# CMSIS-DAP_JX_copy.net
KiCad netlist of a schematic drawn in Altium Designer
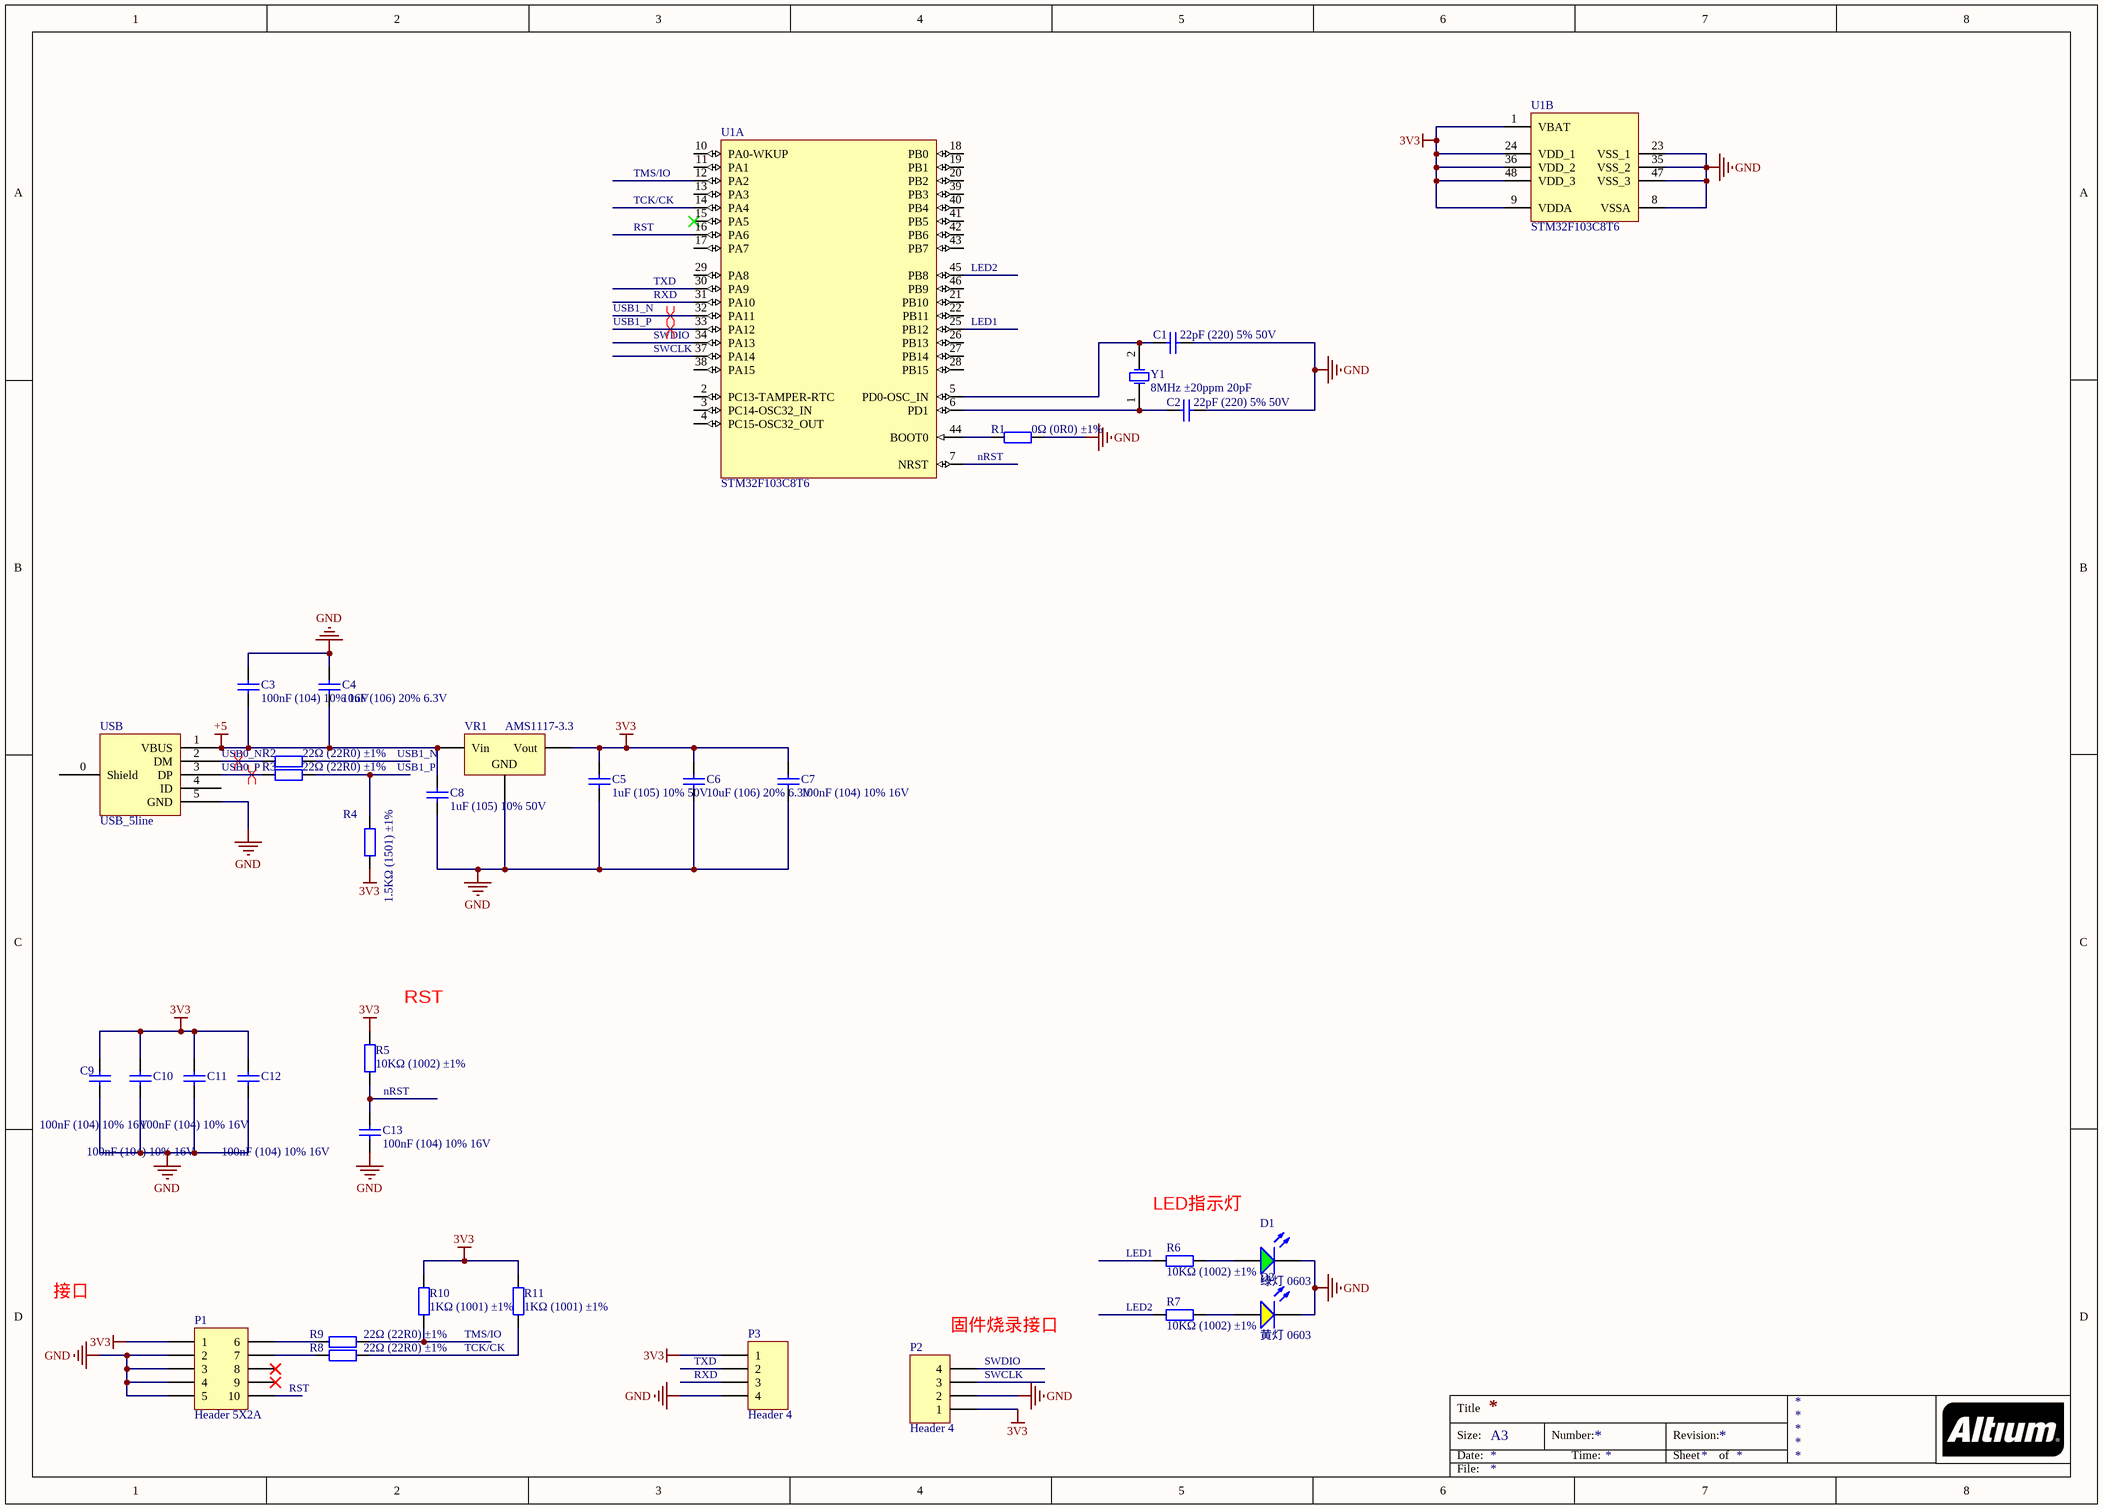
[diagram p0: CMSIS-DAP_JX+copy.schdoc]

(export (version "E")
  (design (tool "Eeschema 10.0.6"))
  (components
    (comp (ref "C1")
      (value "22pF (220) 5% 50V")
      (footprint "0402_C")
      (description "贴片电容")
      (libsource (lib "Miscellaneous Devices LC") (part "0402 22pF (220) 5% 50V"))
    )
    (comp (ref "C2")
      (value "22pF (220) 5% 50V")
      (footprint "0402_C")
      (description "贴片电容")
      (libsource (lib "Miscellaneous Devices LC") (part "0402 22pF (220) 5% 50V"))
    )
    (comp (ref "C3")
      (value "100nF (104) 10% 16V")
      (footprint "0402_C")
      (description "贴片电容")
      (libsource (lib "Miscellaneous Devices LC") (part "0402 100nF (104) 10% 16V"))
    )
    (comp (ref "C4")
      (value "10uF (106) 20% 6.3V")
      (footprint "0402_C")
      (description "贴片电容")
      (libsource (lib "Miscellaneous Devices LC") (part "0402 10uF (106) 20% 6.3V"))
    )
    (comp (ref "C5")
      (value "1uF (105) 10% 50V")
      (footprint "0603_C")
      (description "贴片电容")
      (libsource (lib "Miscellaneous Devices LC") (part "0603 1uF (105) 10% 50V"))
    )
    (comp (ref "C6")
      (value "10uF (106) 20% 6.3V")
      (footprint "0402_C")
      (description "贴片电容")
      (libsource (lib "Miscellaneous Devices LC") (part "0402 10uF (106) 20% 6.3V"))
    )
    (comp (ref "C7")
      (value "100nF (104) 10% 16V")
      (footprint "0402_C")
      (description "贴片电容")
      (libsource (lib "Miscellaneous Devices LC") (part "0402 100nF (104) 10% 16V"))
    )
    (comp (ref "C8")
      (value "1uF (105) 10% 50V")
      (footprint "0603_C")
      (description "贴片电容")
      (libsource (lib "Miscellaneous Devices LC") (part "0603 1uF (105) 10% 50V"))
    )
    (comp (ref "C9")
      (value "100nF (104) 10% 16V")
      (footprint "0402_C")
      (description "贴片电容")
      (libsource (lib "Miscellaneous Devices LC") (part "0402 100nF (104) 10% 16V"))
    )
    (comp (ref "C10")
      (value "100nF (104) 10% 16V")
      (footprint "0402_C")
      (description "贴片电容")
      (libsource (lib "Miscellaneous Devices LC") (part "0402 100nF (104) 10% 16V"))
    )
    (comp (ref "C11")
      (value "100nF (104) 10% 16V")
      (footprint "0402_C")
      (description "贴片电容")
      (libsource (lib "Miscellaneous Devices LC") (part "0402 100nF (104) 10% 16V"))
    )
    (comp (ref "C12")
      (value "100nF (104) 10% 16V")
      (footprint "0402_C")
      (description "贴片电容")
      (libsource (lib "Miscellaneous Devices LC") (part "0402 100nF (104) 10% 16V"))
    )
    (comp (ref "C13")
      (value "100nF (104) 10% 16V")
      (footprint "0402_C")
      (description "贴片电容")
      (libsource (lib "Miscellaneous Devices LC") (part "0402 100nF (104) 10% 16V"))
    )
    (comp (ref "D1")
      (value "绿灯 0603")
      (footprint "0603_LED_S1")
      (description "发光二极管")
      (libsource (lib "Miscellaneous Devices LC") (part "0603 绿灯"))
    )
    (comp (ref "D2")
      (value "黄灯 0603")
      (footprint "0603_LED_S1")
      (description "发光二极管")
      (libsource (lib "Miscellaneous Devices LC") (part "0603 黄灯"))
    )
    (comp (ref "P1")
      (value "Header 5X2A")
      (footprint "SMT HEADER 5*2")
      (description "Header, 5-Pin, Dual row")
      (fields (field (name "PUBLISHER") "Altium Limited"))
      (libsource (lib "Miscellaneous Connectors") (part "Header 5X2A"))
    )
    (comp (ref "P2")
      (value "Header 4")
      (footprint "HDR1X4")
      (description "Header, 4-Pin")
      (fields (field (name "PUBLISHER") "Altium Limited"))
      (libsource (lib "Sparks") (part "Header 4"))
    )
    (comp (ref "P3")
      (value "Header 4")
      (footprint "HDR1X4")
      (description "Header, 4-Pin")
      (fields (field (name "PUBLISHER") "Altium Limited"))
      (libsource (lib "") (part "Header 4_1"))
    )
    (comp (ref "R1")
      (value "0Ω (0R0) ±1%")
      (footprint "0402_R")
      (description "贴片电阻")
      (libsource (lib "Miscellaneous Devices LC") (part "0402 0Ω (0R0) 1%"))
    )
    (comp (ref "R2")
      (value "22Ω (22R0) ±1%")
      (footprint "0402_R")
      (description "贴片电阻")
      (libsource (lib "Miscellaneous Devices LC") (part "0402 22Ω (22R0) 1%"))
    )
    (comp (ref "R3")
      (value "22Ω (22R0) ±1%")
      (footprint "0402_R")
      (description "贴片电阻")
      (libsource (lib "Miscellaneous Devices LC") (part "0402 22Ω (22R0) 1%"))
    )
    (comp (ref "R4")
      (value "1.5KΩ (1501) ±1%")
      (footprint "0402_R")
      (description "贴片电阻")
      (libsource (lib "Miscellaneous Devices LC") (part "0402 1.5KΩ (1501) 1%"))
    )
    (comp (ref "R5")
      (value "10KΩ (1002) ±1%")
      (footprint "0402_R")
      (description "贴片电阻")
      (libsource (lib "") (part "0402 10KΩ (1002) 1%_1"))
    )
    (comp (ref "R6")
      (value "10KΩ (1002) ±1%")
      (footprint "0402_R")
      (description "贴片电阻")
      (libsource (lib "Miscellaneous Devices LC") (part "0402 10KΩ (1002) 1%"))
    )
    (comp (ref "R7")
      (value "10KΩ (1002) ±1%")
      (footprint "0402_R")
      (description "贴片电阻")
      (libsource (lib "Miscellaneous Devices LC") (part "0402 10KΩ (1002) 1%"))
    )
    (comp (ref "R8")
      (value "22Ω (22R0) ±1%")
      (footprint "0402_R")
      (description "贴片电阻")
      (libsource (lib "Miscellaneous Devices LC") (part "0402 22Ω (22R0) 1%"))
    )
    (comp (ref "R9")
      (value "22Ω (22R0) ±1%")
      (footprint "0402_R")
      (description "贴片电阻")
      (libsource (lib "Miscellaneous Devices LC") (part "0402 22Ω (22R0) 1%"))
    )
    (comp (ref "R10")
      (value "1KΩ (1001) ±1%")
      (footprint "0402_R")
      (description "贴片电阻")
      (libsource (lib "Miscellaneous Devices LC") (part "0402 1KΩ (1001) 1%"))
    )
    (comp (ref "R11")
      (value "1KΩ (1001) ±1%")
      (footprint "0402_R")
      (description "贴片电阻")
      (libsource (lib "Miscellaneous Devices LC") (part "0402 1KΩ (1001) 1%"))
    )
    (comp (ref "U1")
      (value "STM32F103C8T6")
      (footprint "LQFP-48_7x7x05P")
      (description "ARM")
      (libsource (lib "Miscellaneous Devices LC") (part "STM32F103C8T6"))
    )
    (comp (ref "USB")
      (value "USB_5line")
      (footprint "USB-MICRO-5P-2F")
      (libsource (lib "2号库") (part "USB_5line"))
    )
    (comp (ref "VR1")
      (value "AMS1117-3.3")
      (footprint "SOT-223")
      (description "低压差线性稳压(LDO)")
      (libsource (lib "Miscellaneous Devices LC") (part "SOT-223 AMS1117-3.3"))
    )
    (comp (ref "Y1")
      (value "8MHz ±20ppm 20pF")
      (footprint "SMD-5032_2P")
      (description "贴片晶振")
      (libsource (lib "Miscellaneous Devices LC") (part "SMD-5032_2P 8MHz 20ppm 20pF"))
    )
  )
  (nets
    (net (code "1") (name "+5") (class "Default")
      (node (ref "C3") (pin "1") (pinfunction "1_1") (pintype "passive"))
      (node (ref "C4") (pin "1") (pinfunction "1_1") (pintype "passive"))
      (node (ref "C8") (pin "2") (pinfunction "2_2") (pintype "passive"))
      (node (ref "USB") (pin "1") (pinfunction "VBUS_1") (pintype "passive"))
      (node (ref "VR1") (pin "3") (pinfunction "Vin_3") (pintype "passive"))
    )
    (net (code "2") (name "/LED1") (class "Default")
      (node (ref "R6") (pin "1") (pinfunction "1_1") (pintype "passive"))
      (node (ref "U1") (pin "25") (pinfunction "PB12_25") (pintype "bidirectional"))
    )
    (net (code "3") (name "/LED2") (class "Default")
      (node (ref "R7") (pin "1") (pinfunction "1_1") (pintype "passive"))
      (node (ref "U1") (pin "45") (pinfunction "PB8_45") (pintype "bidirectional"))
    )
    (net (code "4") (name "/RST") (class "Default")
      (node (ref "P1") (pin "10") (pinfunction "10_10") (pintype "passive"))
      (node (ref "U1") (pin "16") (pinfunction "PA6_16") (pintype "bidirectional"))
    )
    (net (code "5") (name "/RXD") (class "Default")
      (node (ref "P3") (pin "3") (pinfunction "3_3") (pintype "passive"))
      (node (ref "U1") (pin "31") (pinfunction "PA10_31") (pintype "bidirectional"))
    )
    (net (code "6") (name "/SWCLK") (class "Default")
      (node (ref "P2") (pin "3") (pinfunction "3_3") (pintype "passive"))
      (node (ref "U1") (pin "37") (pinfunction "PA14_37") (pintype "bidirectional"))
    )
    (net (code "7") (name "/SWDIO") (class "Default")
      (node (ref "P2") (pin "4") (pinfunction "4_4") (pintype "passive"))
      (node (ref "U1") (pin "34") (pinfunction "PA13_34") (pintype "bidirectional"))
    )
    (net (code "8") (name "/TCK{slash}CK") (class "Default")
      (node (ref "R11") (pin "1") (pinfunction "1_1") (pintype "passive"))
      (node (ref "R8") (pin "2") (pinfunction "2_2") (pintype "passive"))
      (node (ref "U1") (pin "14") (pinfunction "PA4_14") (pintype "bidirectional"))
    )
    (net (code "9") (name "/TMS{slash}IO") (class "Default")
      (node (ref "R10") (pin "1") (pinfunction "1_1") (pintype "passive"))
      (node (ref "R9") (pin "2") (pinfunction "2_2") (pintype "passive"))
      (node (ref "U1") (pin "12") (pinfunction "PA2_12") (pintype "bidirectional"))
    )
    (net (code "10") (name "/TXD") (class "Default")
      (node (ref "P3") (pin "2") (pinfunction "2_2") (pintype "passive"))
      (node (ref "U1") (pin "30") (pinfunction "PA9_30") (pintype "bidirectional"))
    )
    (net (code "11") (name "/USB0_N") (class "Default")
      (node (ref "R2") (pin "1") (pinfunction "1_1") (pintype "passive"))
      (node (ref "USB") (pin "2") (pinfunction "DM_2") (pintype "passive"))
    )
    (net (code "12") (name "/USB0_P") (class "Default")
      (node (ref "R3") (pin "1") (pinfunction "1_1") (pintype "passive"))
      (node (ref "USB") (pin "3") (pinfunction "DP_3") (pintype "passive"))
    )
    (net (code "13") (name "/USB1_N") (class "Default")
      (node (ref "R2") (pin "2") (pinfunction "2_2") (pintype "passive"))
      (node (ref "U1") (pin "32") (pinfunction "PA11_32") (pintype "bidirectional"))
    )
    (net (code "14") (name "/USB1_P") (class "Default")
      (node (ref "R3") (pin "2") (pinfunction "2_2") (pintype "passive"))
      (node (ref "R4") (pin "2") (pinfunction "2_2") (pintype "passive"))
      (node (ref "U1") (pin "33") (pinfunction "PA12_33") (pintype "bidirectional"))
    )
    (net (code "15") (name "/nRST") (class "Default")
      (node (ref "C13") (pin "2") (pinfunction "2_2") (pintype "passive"))
      (node (ref "R5") (pin "1") (pinfunction "1_1") (pintype "passive"))
      (node (ref "U1") (pin "7") (pinfunction "NRST_7") (pintype "bidirectional"))
    )
    (net (code "16") (name "3V3") (class "Default")
      (node (ref "C10") (pin "2") (pinfunction "2_2") (pintype "passive"))
      (node (ref "C11") (pin "2") (pinfunction "2_2") (pintype "passive"))
      (node (ref "C12") (pin "2") (pinfunction "2_2") (pintype "passive"))
      (node (ref "C5") (pin "2") (pinfunction "2_2") (pintype "passive"))
      (node (ref "C6") (pin "2") (pinfunction "2_2") (pintype "passive"))
      (node (ref "C7") (pin "2") (pinfunction "2_2") (pintype "passive"))
      (node (ref "C9") (pin "2") (pinfunction "2_2") (pintype "passive"))
      (node (ref "P1") (pin "1") (pinfunction "1_1") (pintype "passive"))
      (node (ref "P2") (pin "1") (pinfunction "1_1") (pintype "passive"))
      (node (ref "P3") (pin "1") (pinfunction "1_1") (pintype "passive"))
      (node (ref "R10") (pin "2") (pinfunction "2_2") (pintype "passive"))
      (node (ref "R11") (pin "2") (pinfunction "2_2") (pintype "passive"))
      (node (ref "R4") (pin "1") (pinfunction "1_1") (pintype "passive"))
      (node (ref "R5") (pin "2") (pinfunction "2_2") (pintype "passive"))
      (node (ref "U1") (pin "1") (pinfunction "VBAT_1") (pintype "power_in"))
      (node (ref "U1") (pin "24") (pinfunction "VDD_1_24") (pintype "power_in"))
      (node (ref "U1") (pin "36") (pinfunction "VDD_2_36") (pintype "power_in"))
      (node (ref "U1") (pin "48") (pinfunction "VDD_3_48") (pintype "power_in"))
      (node (ref "U1") (pin "9") (pinfunction "VDDA_9") (pintype "power_in"))
      (node (ref "VR1") (pin "2") (pinfunction "Vout_2") (pintype "passive"))
    )
    (net (code "17") (name "GND") (class "Default")
      (node (ref "C1") (pin "2") (pinfunction "2_2") (pintype "passive"))
      (node (ref "C10") (pin "1") (pinfunction "1_1") (pintype "passive"))
      (node (ref "C11") (pin "1") (pinfunction "1_1") (pintype "passive"))
      (node (ref "C12") (pin "1") (pinfunction "1_1") (pintype "passive"))
      (node (ref "C13") (pin "1") (pinfunction "1_1") (pintype "passive"))
      (node (ref "C2") (pin "2") (pinfunction "2_2") (pintype "passive"))
      (node (ref "C3") (pin "2") (pinfunction "2_2") (pintype "passive"))
      (node (ref "C4") (pin "2") (pinfunction "2_2") (pintype "passive"))
      (node (ref "C5") (pin "1") (pinfunction "1_1") (pintype "passive"))
      (node (ref "C6") (pin "1") (pinfunction "1_1") (pintype "passive"))
      (node (ref "C7") (pin "1") (pinfunction "1_1") (pintype "passive"))
      (node (ref "C8") (pin "1") (pinfunction "1_1") (pintype "passive"))
      (node (ref "C9") (pin "1") (pinfunction "1_1") (pintype "passive"))
      (node (ref "D1") (pin "K") (pinfunction "K_K") (pintype "passive"))
      (node (ref "D2") (pin "K") (pinfunction "K_K") (pintype "passive"))
      (node (ref "P1") (pin "2") (pinfunction "2_2") (pintype "passive"))
      (node (ref "P1") (pin "3") (pinfunction "3_3") (pintype "passive"))
      (node (ref "P1") (pin "4") (pinfunction "4_4") (pintype "passive"))
      (node (ref "P1") (pin "5") (pinfunction "5_5") (pintype "passive"))
      (node (ref "P2") (pin "2") (pinfunction "2_2") (pintype "passive"))
      (node (ref "P3") (pin "4") (pinfunction "4_4") (pintype "passive"))
      (node (ref "R1") (pin "2") (pinfunction "2_2") (pintype "passive"))
      (node (ref "U1") (pin "23") (pinfunction "VSS_1_23") (pintype "power_in"))
      (node (ref "U1") (pin "35") (pinfunction "VSS_2_35") (pintype "power_in"))
      (node (ref "U1") (pin "47") (pinfunction "VSS_3_47") (pintype "power_in"))
      (node (ref "U1") (pin "8") (pinfunction "VSSA_8") (pintype "power_in"))
      (node (ref "USB") (pin "5") (pinfunction "GND_5") (pintype "passive"))
      (node (ref "VR1") (pin "1") (pinfunction "GND_1") (pintype "passive"))
    )
    (net (code "18") (name "Net-(D1-PadA)") (class "Default")
      (node (ref "D1") (pin "A") (pinfunction "A_A") (pintype "passive"))
      (node (ref "R6") (pin "2") (pinfunction "2_2") (pintype "passive"))
    )
    (net (code "19") (name "Net-(D2-PadA)") (class "Default")
      (node (ref "D2") (pin "A") (pinfunction "A_A") (pintype "passive"))
      (node (ref "R7") (pin "2") (pinfunction "2_2") (pintype "passive"))
    )
    (net (code "20") (name "Net-(P1-Pad6)") (class "Default")
      (node (ref "P1") (pin "6") (pinfunction "6_6") (pintype "passive"))
      (node (ref "R9") (pin "1") (pinfunction "1_1") (pintype "passive"))
    )
    (net (code "21") (name "Net-(P1-Pad7)") (class "Default")
      (node (ref "P1") (pin "7") (pinfunction "7_7") (pintype "passive"))
      (node (ref "R8") (pin "1") (pinfunction "1_1") (pintype "passive"))
    )
    (net (code "22") (name "Net-(U1A-BOOT0)") (class "Default")
      (node (ref "R1") (pin "1") (pinfunction "1_1") (pintype "passive"))
      (node (ref "U1") (pin "44") (pinfunction "BOOT0_44") (pintype "input"))
    )
    (net (code "23") (name "Net-(U1A-PD0-OSC_IN)") (class "Default")
      (node (ref "C1") (pin "1") (pinfunction "1_1") (pintype "passive"))
      (node (ref "U1") (pin "5") (pinfunction "PD0-OSC_IN_5") (pintype "bidirectional"))
      (node (ref "Y1") (pin "2") (pinfunction "OSC2_2") (pintype "passive"))
    )
    (net (code "24") (name "Net-(U1A-PD1)") (class "Default")
      (node (ref "C2") (pin "1") (pinfunction "1_1") (pintype "passive"))
      (node (ref "U1") (pin "6") (pinfunction "PD1_6") (pintype "bidirectional"))
      (node (ref "Y1") (pin "1") (pinfunction "OSC1_1") (pintype "passive"))
    )
    (net (code "25") (name "unconnected-(P1-Pad8)") (class "Default")
      (node (ref "P1") (pin "8") (pinfunction "8_8") (pintype "passive+no_connect"))
    )
    (net (code "26") (name "unconnected-(P1-Pad9)") (class "Default")
      (node (ref "P1") (pin "9") (pinfunction "9_9") (pintype "passive+no_connect"))
    )
    (net (code "27") (name "unconnected-(U1A-PA0-WKUP-Pad10)") (class "Default")
      (node (ref "U1") (pin "10") (pinfunction "PA0-WKUP_10") (pintype "bidirectional"))
    )
    (net (code "28") (name "unconnected-(U1A-PA1-Pad11)") (class "Default")
      (node (ref "U1") (pin "11") (pinfunction "PA1_11") (pintype "bidirectional"))
    )
    (net (code "29") (name "unconnected-(U1A-PA3-Pad13)") (class "Default")
      (node (ref "U1") (pin "13") (pinfunction "PA3_13") (pintype "bidirectional"))
    )
    (net (code "30") (name "unconnected-(U1A-PA5-Pad15)") (class "Default")
      (node (ref "U1") (pin "15") (pinfunction "PA5_15") (pintype "bidirectional+no_connect"))
    )
    (net (code "31") (name "unconnected-(U1A-PA7-Pad17)") (class "Default")
      (node (ref "U1") (pin "17") (pinfunction "PA7_17") (pintype "bidirectional"))
    )
    (net (code "32") (name "unconnected-(U1A-PA8-Pad29)") (class "Default")
      (node (ref "U1") (pin "29") (pinfunction "PA8_29") (pintype "bidirectional"))
    )
    (net (code "33") (name "unconnected-(U1A-PA15-Pad38)") (class "Default")
      (node (ref "U1") (pin "38") (pinfunction "PA15_38") (pintype "bidirectional"))
    )
    (net (code "34") (name "unconnected-(U1A-PB0-Pad18)") (class "Default")
      (node (ref "U1") (pin "18") (pinfunction "PB0_18") (pintype "bidirectional"))
    )
    (net (code "35") (name "unconnected-(U1A-PB1-Pad19)") (class "Default")
      (node (ref "U1") (pin "19") (pinfunction "PB1_19") (pintype "bidirectional"))
    )
    (net (code "36") (name "unconnected-(U1A-PB2-Pad20)") (class "Default")
      (node (ref "U1") (pin "20") (pinfunction "PB2_20") (pintype "bidirectional"))
    )
    (net (code "37") (name "unconnected-(U1A-PB3-Pad39)") (class "Default")
      (node (ref "U1") (pin "39") (pinfunction "PB3_39") (pintype "bidirectional"))
    )
    (net (code "38") (name "unconnected-(U1A-PB4-Pad40)") (class "Default")
      (node (ref "U1") (pin "40") (pinfunction "PB4_40") (pintype "bidirectional"))
    )
    (net (code "39") (name "unconnected-(U1A-PB5-Pad41)") (class "Default")
      (node (ref "U1") (pin "41") (pinfunction "PB5_41") (pintype "bidirectional"))
    )
    (net (code "40") (name "unconnected-(U1A-PB6-Pad42)") (class "Default")
      (node (ref "U1") (pin "42") (pinfunction "PB6_42") (pintype "bidirectional"))
    )
    (net (code "41") (name "unconnected-(U1A-PB7-Pad43)") (class "Default")
      (node (ref "U1") (pin "43") (pinfunction "PB7_43") (pintype "bidirectional"))
    )
    (net (code "42") (name "unconnected-(U1A-PB9-Pad46)") (class "Default")
      (node (ref "U1") (pin "46") (pinfunction "PB9_46") (pintype "bidirectional"))
    )
    (net (code "43") (name "unconnected-(U1A-PB10-Pad21)") (class "Default")
      (node (ref "U1") (pin "21") (pinfunction "PB10_21") (pintype "bidirectional"))
    )
    (net (code "44") (name "unconnected-(U1A-PB11-Pad22)") (class "Default")
      (node (ref "U1") (pin "22") (pinfunction "PB11_22") (pintype "bidirectional"))
    )
    (net (code "45") (name "unconnected-(U1A-PB13-Pad26)") (class "Default")
      (node (ref "U1") (pin "26") (pinfunction "PB13_26") (pintype "bidirectional"))
    )
    (net (code "46") (name "unconnected-(U1A-PB14-Pad27)") (class "Default")
      (node (ref "U1") (pin "27") (pinfunction "PB14_27") (pintype "bidirectional"))
    )
    (net (code "47") (name "unconnected-(U1A-PB15-Pad28)") (class "Default")
      (node (ref "U1") (pin "28") (pinfunction "PB15_28") (pintype "bidirectional"))
    )
    (net (code "48") (name "unconnected-(U1A-PC13-TAMPER-RTC-Pad2)") (class "Default")
      (node (ref "U1") (pin "2") (pinfunction "PC13-TAMPER-RTC_2") (pintype "bidirectional"))
    )
    (net (code "49") (name "unconnected-(U1A-PC14-OSC32_IN-Pad3)") (class "Default")
      (node (ref "U1") (pin "3") (pinfunction "PC14-OSC32_IN_3") (pintype "bidirectional"))
    )
    (net (code "50") (name "unconnected-(U1A-PC15-OSC32_OUT-Pad4)") (class "Default")
      (node (ref "U1") (pin "4") (pinfunction "PC15-OSC32_OUT_4") (pintype "bidirectional"))
    )
    (net (code "51") (name "unconnected-(USB-ID-Pad4)") (class "Default")
      (node (ref "USB") (pin "4") (pinfunction "ID_4") (pintype "passive"))
    )
    (net (code "52") (name "unconnected-(USB-Shield-Pad0)") (class "Default")
      (node (ref "USB") (pin "0") (pinfunction "Shield_0") (pintype "passive"))
    )
  )
)
